# JS7628_base_usb_hub_v1_0.net
KiCad netlist of a schematic drawn in Altium Designer
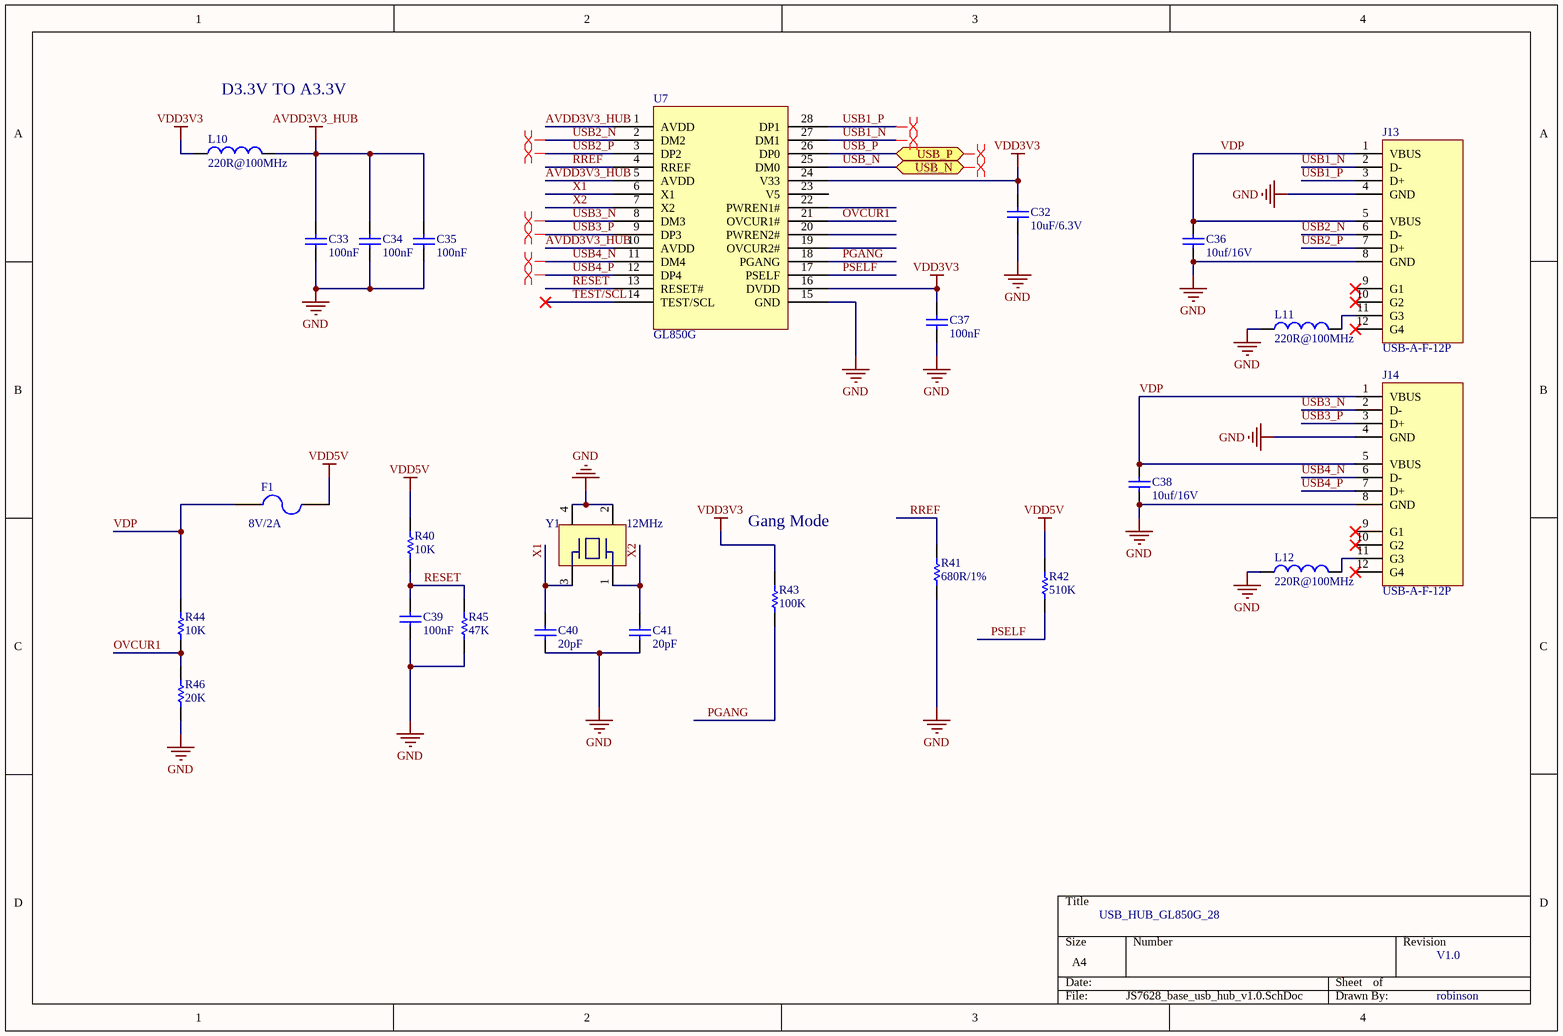
[diagram p0: JS7628_base_usb_hub_v1.0.SchDoc]

(export (version "E")
  (design (tool "Eeschema 10.0.6"))
  (components
    (comp (ref "C32")
      (value "10uF/6.3V")
      (footprint "0603")
      (fields (field (name "Comment") "CAP-SMT"))
      (libsource (lib "MyMiscellaneousDevice") (part "CAP-SMT"))
    )
    (comp (ref "C33")
      (value "100nF")
      (footprint "0603")
      (fields (field (name "Comment") "CAP-SMT"))
      (libsource (lib "MyMiscellaneousDevice") (part "CAP-SMT"))
    )
    (comp (ref "C34")
      (value "100nF")
      (footprint "0603")
      (fields (field (name "Comment") "CAP-SMT"))
      (libsource (lib "MyMiscellaneousDevice") (part "CAP-SMT"))
    )
    (comp (ref "C35")
      (value "100nF")
      (footprint "0603")
      (fields (field (name "Comment") "CAP-SMT"))
      (libsource (lib "MyMiscellaneousDevice") (part "CAP-SMT"))
    )
    (comp (ref "C36")
      (value "10uf/16V")
      (footprint "0603")
      (fields (field (name "Comment") "CAP-SMT"))
      (libsource (lib "MyMiscellaneousDevice") (part "CAP-SMT"))
    )
    (comp (ref "C37")
      (value "100nF")
      (footprint "0603")
      (fields (field (name "Comment") "CAP-SMT"))
      (libsource (lib "MyMiscellaneousDevice") (part "CAP-SMT"))
    )
    (comp (ref "C38")
      (value "10uf/16V")
      (footprint "0603")
      (fields (field (name "Comment") "CAP-SMT"))
      (libsource (lib "MyMiscellaneousDevice") (part "CAP-SMT"))
    )
    (comp (ref "C39")
      (value "100nF")
      (footprint "0603")
      (fields (field (name "Comment") "CAP-SMT"))
      (libsource (lib "MyMiscellaneousDevice") (part "CAP-SMT"))
    )
    (comp (ref "C40")
      (value "20pF")
      (footprint "0603")
      (fields (field (name "Comment") "CAP-SMT"))
      (libsource (lib "MyMiscellaneousDevice") (part "CAP-SMT"))
    )
    (comp (ref "C41")
      (value "20pF")
      (footprint "0603")
      (fields (field (name "Comment") "CAP-SMT"))
      (libsource (lib "MyMiscellaneousDevice") (part "CAP-SMT"))
    )
    (comp (ref "F1")
      (value "8V/2A")
      (footprint "1812")
      (fields (field (name "Comment") "FUSE"))
      (libsource (lib "MyMiscellaneousDevice") (part "FUSE"))
    )
    (comp (ref "J13")
      (value "USB-A-F-12P")
      (footprint "USB-A-F-12P-90D")
      (libsource (lib "MyMiscellaneousConnector") (part "USB-A-F-12P"))
    )
    (comp (ref "J14")
      (value "USB-A-F-12P")
      (footprint "USB-A-F-12P-90D")
      (libsource (lib "MyMiscellaneousConnector") (part "USB-A-F-12P"))
    )
    (comp (ref "L10")
      (value "220R@100MHz")
      (footprint "0603")
      (fields (field (name "Comment") "inductor"))
      (libsource (lib "MyMiscellaneousDevice") (part "inductor"))
    )
    (comp (ref "L11")
      (value "220R@100MHz")
      (footprint "0603")
      (fields (field (name "Comment") "inductor"))
      (libsource (lib "MyMiscellaneousDevice") (part "inductor"))
    )
    (comp (ref "L12")
      (value "220R@100MHz")
      (footprint "0603")
      (fields (field (name "Comment") "inductor"))
      (libsource (lib "MyMiscellaneousDevice") (part "inductor"))
    )
    (comp (ref "R40")
      (value "10K")
      (footprint "0603")
      (fields (field (name "Comment") "RES-SMT"))
      (libsource (lib "MyMiscellaneousDevice") (part "RES-SMT"))
    )
    (comp (ref "R41")
      (value "680R/1%")
      (footprint "0603")
      (fields (field (name "Comment") "RES-SMT"))
      (libsource (lib "MyMiscellaneousDevice") (part "RES-SMT"))
    )
    (comp (ref "R42")
      (value "510K")
      (footprint "0603")
      (fields (field (name "Comment") "RES-SMT"))
      (libsource (lib "MyMiscellaneousDevice") (part "RES-SMT"))
    )
    (comp (ref "R43")
      (value "100K")
      (footprint "0603")
      (fields (field (name "Comment") "RES-SMT"))
      (libsource (lib "MyMiscellaneousDevice") (part "RES-SMT"))
    )
    (comp (ref "R44")
      (value "10K")
      (footprint "0603")
      (fields (field (name "Comment") "RES-SMT"))
      (libsource (lib "MyMiscellaneousDevice") (part "RES-SMT"))
    )
    (comp (ref "R45")
      (value "47K")
      (footprint "0603")
      (fields (field (name "Comment") "RES-SMT"))
      (libsource (lib "MyMiscellaneousDevice") (part "RES-SMT"))
    )
    (comp (ref "R46")
      (value "20K")
      (footprint "0603")
      (fields (field (name "Comment") "RES-SMT"))
      (libsource (lib "MyMiscellaneousDevice") (part "RES-SMT"))
    )
    (comp (ref "U7")
      (value "GL850G")
      (footprint "SSOP28")
      (libsource (lib "MyMiscellaneousDevice") (part "GL850G"))
    )
    (comp (ref "Y1")
      (value "12MHz")
      (footprint "3225-4P")
      (fields (field (name "Comment") "XTAL-4p"))
      (libsource (lib "MyMiscellaneousDevice") (part "XTAL-4p"))
    )
  )
  (nets
    (net (code "1") (name "/OVCUR1") (class "Default")
      (node (ref "R44") (pin "1") (pinfunction "1_1") (pintype "passive"))
      (node (ref "R46") (pin "2") (pinfunction "2_2") (pintype "passive"))
      (node (ref "U7") (pin "21") (pinfunction "OVCUR1#_21") (pintype "passive"))
    )
    (net (code "2") (name "/PGANG") (class "Default")
      (node (ref "R43") (pin "1") (pinfunction "1_1") (pintype "passive"))
      (node (ref "U7") (pin "18") (pinfunction "PGANG_18") (pintype "passive"))
    )
    (net (code "3") (name "/PSELF") (class "Default")
      (node (ref "R42") (pin "1") (pinfunction "1_1") (pintype "passive"))
      (node (ref "U7") (pin "17") (pinfunction "PSELF_17") (pintype "passive"))
    )
    (net (code "4") (name "/RESET") (class "Default")
      (node (ref "C39") (pin "2") (pinfunction "2_2") (pintype "passive"))
      (node (ref "R40") (pin "1") (pinfunction "1_1") (pintype "passive"))
      (node (ref "R45") (pin "2") (pinfunction "2_2") (pintype "passive"))
      (node (ref "U7") (pin "13") (pinfunction "RESET#_13") (pintype "passive"))
    )
    (net (code "5") (name "/RREF") (class "Default")
      (node (ref "R41") (pin "2") (pinfunction "2_2") (pintype "passive"))
      (node (ref "U7") (pin "4") (pinfunction "RREF_4") (pintype "passive"))
    )
    (net (code "6") (name "/TEST{slash}SCL") (class "Default")
      (node (ref "U7") (pin "14") (pinfunction "TEST/SCL_14") (pintype "passive+no_connect"))
    )
    (net (code "7") (name "/USB1_N") (class "Default")
      (node (ref "J13") (pin "2") (pinfunction "D-_2") (pintype "passive"))
      (node (ref "U7") (pin "27") (pinfunction "DM1_27") (pintype "passive"))
    )
    (net (code "8") (name "/USB1_P") (class "Default")
      (node (ref "J13") (pin "3") (pinfunction "D+_3") (pintype "passive"))
      (node (ref "U7") (pin "28") (pinfunction "DP1_28") (pintype "passive"))
    )
    (net (code "9") (name "/USB2_N") (class "Default")
      (node (ref "J13") (pin "6") (pinfunction "D-_6") (pintype "passive"))
      (node (ref "U7") (pin "2") (pinfunction "DM2_2") (pintype "passive"))
    )
    (net (code "10") (name "/USB2_P") (class "Default")
      (node (ref "J13") (pin "7") (pinfunction "D+_7") (pintype "passive"))
      (node (ref "U7") (pin "3") (pinfunction "DP2_3") (pintype "passive"))
    )
    (net (code "11") (name "/USB3_N") (class "Default")
      (node (ref "J14") (pin "2") (pinfunction "D-_2") (pintype "passive"))
      (node (ref "U7") (pin "8") (pinfunction "DM3_8") (pintype "passive"))
    )
    (net (code "12") (name "/USB3_P") (class "Default")
      (node (ref "J14") (pin "3") (pinfunction "D+_3") (pintype "passive"))
      (node (ref "U7") (pin "9") (pinfunction "DP3_9") (pintype "passive"))
    )
    (net (code "13") (name "/USB4_N") (class "Default")
      (node (ref "J14") (pin "6") (pinfunction "D-_6") (pintype "passive"))
      (node (ref "U7") (pin "11") (pinfunction "DM4_11") (pintype "passive"))
    )
    (net (code "14") (name "/USB4_P") (class "Default")
      (node (ref "J14") (pin "7") (pinfunction "D+_7") (pintype "passive"))
      (node (ref "U7") (pin "12") (pinfunction "DP4_12") (pintype "passive"))
    )
    (net (code "15") (name "/USB_N") (class "Default")
      (node (ref "U7") (pin "25") (pinfunction "DM0_25") (pintype "passive"))
    )
    (net (code "16") (name "/USB_P") (class "Default")
      (node (ref "U7") (pin "26") (pinfunction "DP0_26") (pintype "passive"))
    )
    (net (code "17") (name "/VDP") (class "Default")
      (node (ref "C36") (pin "2") (pinfunction "2_2") (pintype "passive"))
      (node (ref "C38") (pin "2") (pinfunction "2_2") (pintype "passive"))
      (node (ref "F1") (pin "1") (pinfunction "1_1") (pintype "passive"))
      (node (ref "J13") (pin "1") (pinfunction "VBUS_1") (pintype "passive"))
      (node (ref "J13") (pin "5") (pinfunction "VBUS_5") (pintype "passive"))
      (node (ref "J14") (pin "1") (pinfunction "VBUS_1") (pintype "passive"))
      (node (ref "J14") (pin "5") (pinfunction "VBUS_5") (pintype "passive"))
      (node (ref "R44") (pin "2") (pinfunction "2_2") (pintype "passive"))
    )
    (net (code "18") (name "/X1") (class "Default")
      (node (ref "C40") (pin "2") (pinfunction "2_2") (pintype "passive"))
      (node (ref "U7") (pin "6") (pinfunction "X1_6") (pintype "passive"))
      (node (ref "Y1") (pin "3") (pinfunction "3_3") (pintype "passive"))
    )
    (net (code "19") (name "/X2") (class "Default")
      (node (ref "C41") (pin "2") (pinfunction "2_2") (pintype "passive"))
      (node (ref "U7") (pin "7") (pinfunction "X2_7") (pintype "passive"))
      (node (ref "Y1") (pin "1") (pinfunction "0_1") (pintype "passive"))
    )
    (net (code "20") (name "AVDD3V3_HUB") (class "Default")
      (node (ref "C33") (pin "2") (pinfunction "2_2") (pintype "passive"))
      (node (ref "C34") (pin "2") (pinfunction "2_2") (pintype "passive"))
      (node (ref "C35") (pin "2") (pinfunction "2_2") (pintype "passive"))
      (node (ref "L10") (pin "2") (pinfunction "2_2") (pintype "passive"))
      (node (ref "U7") (pin "1") (pinfunction "AVDD_1") (pintype "passive"))
      (node (ref "U7") (pin "10") (pinfunction "AVDD_10") (pintype "passive"))
      (node (ref "U7") (pin "5") (pinfunction "AVDD_5") (pintype "passive"))
    )
    (net (code "21") (name "GND") (class "Default")
      (node (ref "C32") (pin "1") (pinfunction "1_1") (pintype "passive"))
      (node (ref "C33") (pin "1") (pinfunction "1_1") (pintype "passive"))
      (node (ref "C34") (pin "1") (pinfunction "1_1") (pintype "passive"))
      (node (ref "C35") (pin "1") (pinfunction "1_1") (pintype "passive"))
      (node (ref "C36") (pin "1") (pinfunction "1_1") (pintype "passive"))
      (node (ref "C37") (pin "1") (pinfunction "1_1") (pintype "passive"))
      (node (ref "C38") (pin "1") (pinfunction "1_1") (pintype "passive"))
      (node (ref "C39") (pin "1") (pinfunction "1_1") (pintype "passive"))
      (node (ref "C40") (pin "1") (pinfunction "1_1") (pintype "passive"))
      (node (ref "C41") (pin "1") (pinfunction "1_1") (pintype "passive"))
      (node (ref "J13") (pin "4") (pinfunction "GND_4") (pintype "passive"))
      (node (ref "J13") (pin "8") (pinfunction "GND_8") (pintype "passive"))
      (node (ref "J14") (pin "4") (pinfunction "GND_4") (pintype "passive"))
      (node (ref "J14") (pin "8") (pinfunction "GND_8") (pintype "passive"))
      (node (ref "L11") (pin "1") (pinfunction "1_1") (pintype "passive"))
      (node (ref "L12") (pin "1") (pinfunction "1_1") (pintype "passive"))
      (node (ref "R41") (pin "1") (pinfunction "1_1") (pintype "passive"))
      (node (ref "R45") (pin "1") (pinfunction "1_1") (pintype "passive"))
      (node (ref "R46") (pin "1") (pinfunction "1_1") (pintype "passive"))
      (node (ref "U7") (pin "15") (pinfunction "GND_15") (pintype "passive"))
      (node (ref "Y1") (pin "2") (pinfunction "2_2") (pintype "passive"))
      (node (ref "Y1") (pin "4") (pinfunction "4_4") (pintype "passive"))
    )
    (net (code "22") (name "Net-(J13-G3)") (class "Default")
      (node (ref "J13") (pin "11") (pinfunction "G3_11") (pintype "passive"))
      (node (ref "L11") (pin "2") (pinfunction "2_2") (pintype "passive"))
    )
    (net (code "23") (name "Net-(J14-G3)") (class "Default")
      (node (ref "J14") (pin "11") (pinfunction "G3_11") (pintype "passive"))
      (node (ref "L12") (pin "2") (pinfunction "2_2") (pintype "passive"))
    )
    (net (code "24") (name "VDD3V3") (class "Default")
      (node (ref "C32") (pin "2") (pinfunction "2_2") (pintype "passive"))
      (node (ref "C37") (pin "2") (pinfunction "2_2") (pintype "passive"))
      (node (ref "L10") (pin "1") (pinfunction "1_1") (pintype "passive"))
      (node (ref "R43") (pin "2") (pinfunction "2_2") (pintype "passive"))
      (node (ref "U7") (pin "16") (pinfunction "DVDD_16") (pintype "passive"))
      (node (ref "U7") (pin "24") (pinfunction "V33_24") (pintype "passive"))
    )
    (net (code "25") (name "VDD5V") (class "Default")
      (node (ref "F1") (pin "2") (pinfunction "2_2") (pintype "passive"))
      (node (ref "R40") (pin "2") (pinfunction "2_2") (pintype "passive"))
      (node (ref "R42") (pin "2") (pinfunction "2_2") (pintype "passive"))
    )
    (net (code "26") (name "unconnected-(J13-G1-Pad9)") (class "Default")
      (node (ref "J13") (pin "9") (pinfunction "G1_9") (pintype "passive+no_connect"))
    )
    (net (code "27") (name "unconnected-(J13-G2-Pad10)") (class "Default")
      (node (ref "J13") (pin "10") (pinfunction "G2_10") (pintype "passive+no_connect"))
    )
    (net (code "28") (name "unconnected-(J13-G4-Pad12)") (class "Default")
      (node (ref "J13") (pin "12") (pinfunction "G4_12") (pintype "passive+no_connect"))
    )
    (net (code "29") (name "unconnected-(J14-G1-Pad9)") (class "Default")
      (node (ref "J14") (pin "9") (pinfunction "G1_9") (pintype "passive+no_connect"))
    )
    (net (code "30") (name "unconnected-(J14-G2-Pad10)") (class "Default")
      (node (ref "J14") (pin "10") (pinfunction "G2_10") (pintype "passive+no_connect"))
    )
    (net (code "31") (name "unconnected-(J14-G4-Pad12)") (class "Default")
      (node (ref "J14") (pin "12") (pinfunction "G4_12") (pintype "passive+no_connect"))
    )
    (net (code "32") (name "unconnected-(U7-OVCUR2#-Pad19)") (class "Default")
      (node (ref "U7") (pin "19") (pinfunction "OVCUR2#_19") (pintype "passive"))
    )
    (net (code "33") (name "unconnected-(U7-PWREN1#-Pad22)") (class "Default")
      (node (ref "U7") (pin "22") (pinfunction "PWREN1#_22") (pintype "passive"))
    )
    (net (code "34") (name "unconnected-(U7-PWREN2#-Pad20)") (class "Default")
      (node (ref "U7") (pin "20") (pinfunction "PWREN2#_20") (pintype "passive"))
    )
    (net (code "35") (name "unconnected-(U7-V5-Pad23)") (class "Default")
      (node (ref "U7") (pin "23") (pinfunction "V5_23") (pintype "passive"))
    )
  )
)
